# Adafruit_Flora_TCS34725.net
KiCad netlist of a schematic drawn in EAGLE
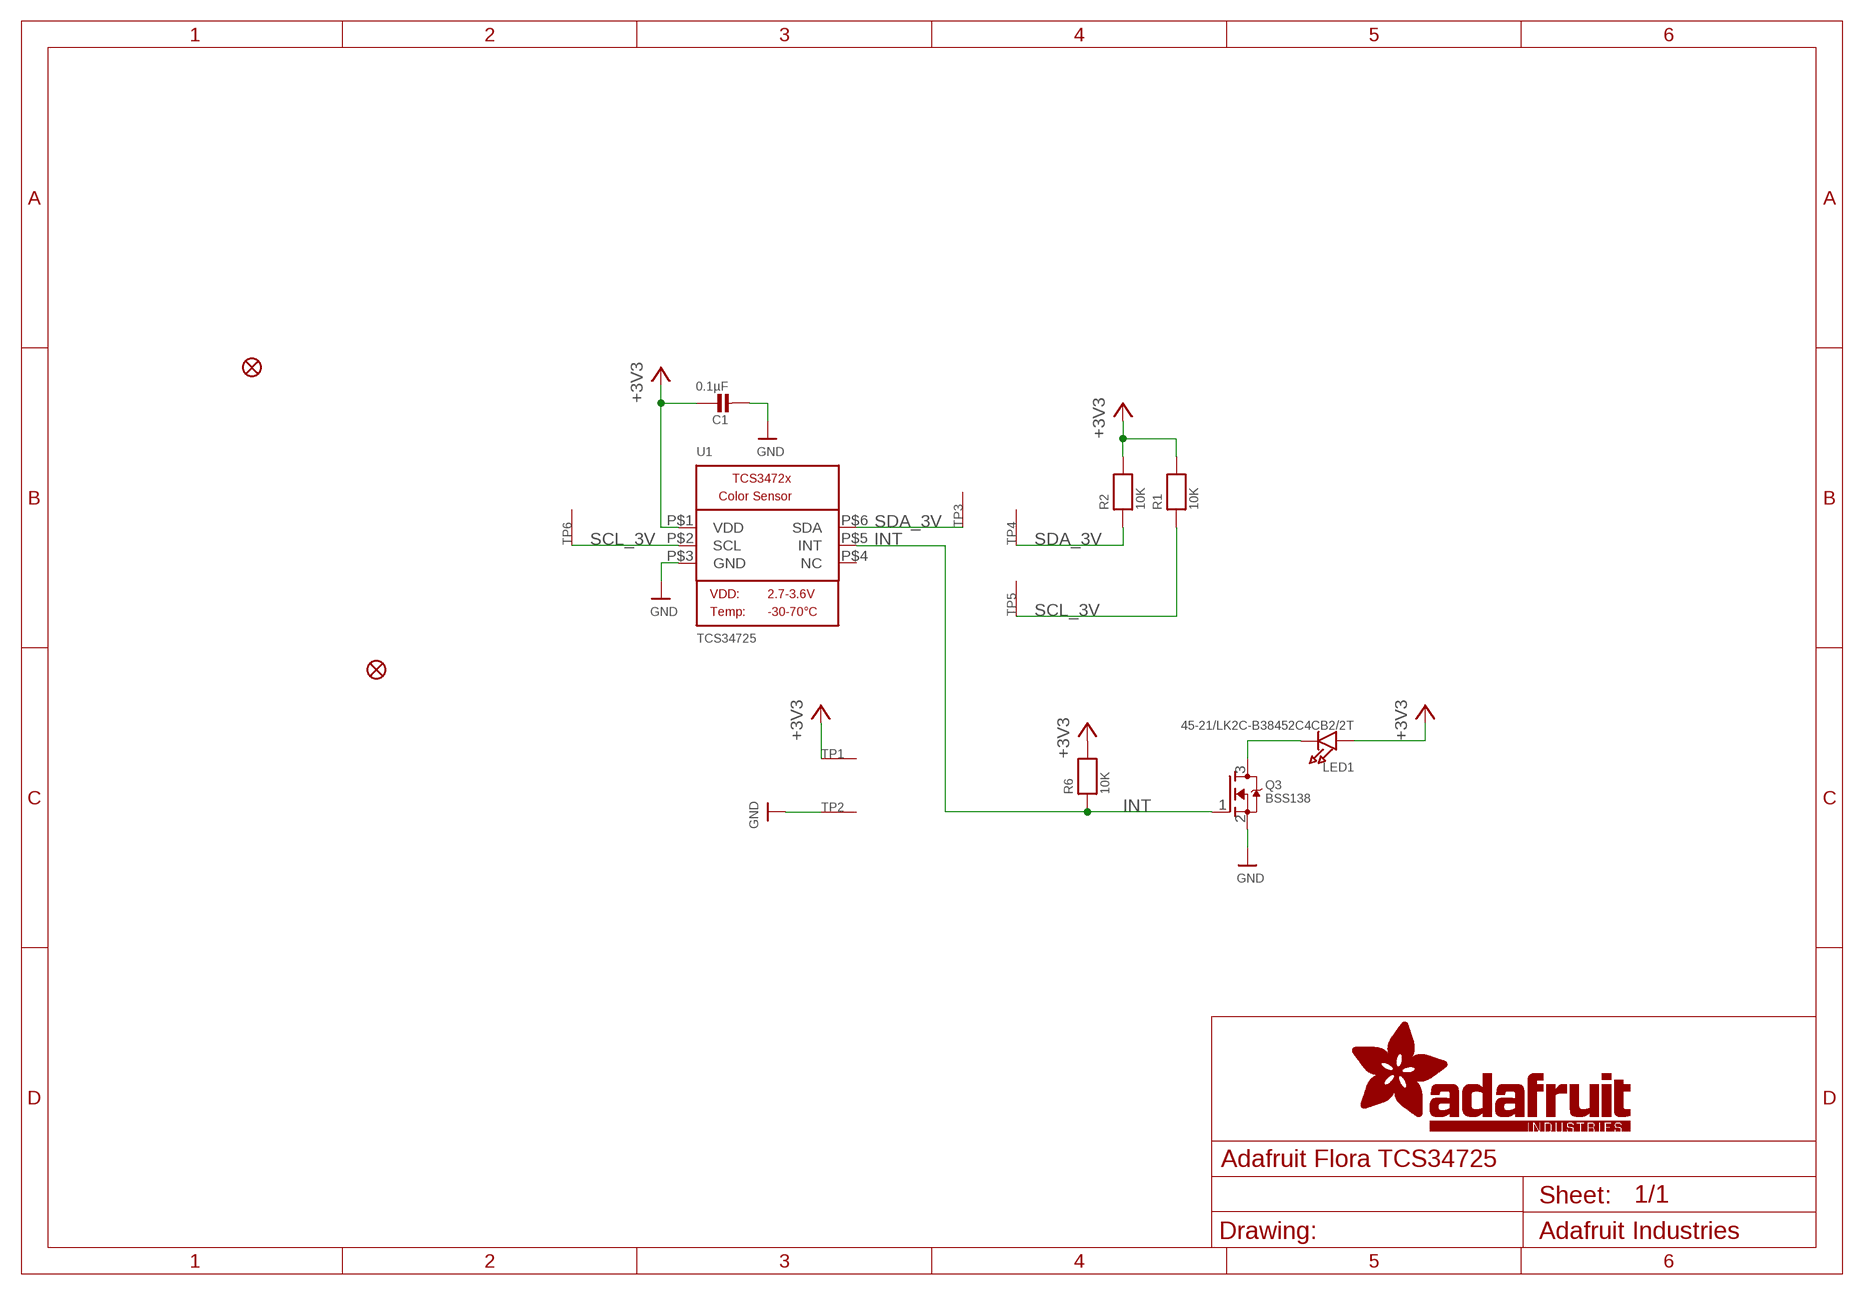
[diagram p0: schematic, sheet 1]

(export (version "E")
  (design (tool "Eeschema 10.0.6"))
  (components
    (comp (ref "C1")
      (value "0.1µF")
      (footprint "eagle-import:_0805")
      (libsource (lib "eagle-import") (part "CAP_CERAMIC_0805"))
    )
    (comp (ref "FID1")
      (value "FIDUCIAL\"\"")
      (footprint "eagle-import:FIDUCIAL_1MM")
      (libsource (lib "eagle-import") (part "FIDUCIAL{dblquote}{dblquote}"))
    )
    (comp (ref "FID2")
      (value "FIDUCIAL\"\"")
      (footprint "eagle-import:FIDUCIAL_1MM")
      (libsource (lib "eagle-import") (part "FIDUCIAL{dblquote}{dblquote}"))
    )
    (comp (ref "LED1")
      (value "45-21/LK2C-B38452C4CB2/2T")
      (footprint "eagle-import:EVERLIGHT_45-21")
      (libsource (lib "eagle-import") (part "LEDEV45-21"))
    )
    (comp (ref "Q3")
      (value "BSS138")
      (footprint "eagle-import:SOT23-WIDE")
      (libsource (lib "eagle-import") (part "MOSFET-NWIDE"))
    )
    (comp (ref "R1")
      (value "10K")
      (footprint "eagle-import:_0805")
      (libsource (lib "eagle-import") (part "RESISTOR_0805"))
    )
    (comp (ref "R2")
      (value "10K")
      (footprint "eagle-import:_0805")
      (libsource (lib "eagle-import") (part "RESISTOR_0805"))
    )
    (comp (ref "R6")
      (value "10K")
      (footprint "eagle-import:_0805")
      (libsource (lib "eagle-import") (part "RESISTOR_0805"))
    )
    (comp (ref "TP1")
      (value "SEWTAP0.5IN")
      (footprint "eagle-import:SEWINGTAP_0.5")
      (libsource (lib "eagle-import") (part "SEWTAP0.5IN"))
    )
    (comp (ref "TP2")
      (value "SEWTAP0.5IN")
      (footprint "eagle-import:SEWINGTAP_0.5")
      (libsource (lib "eagle-import") (part "SEWTAP0.5IN"))
    )
    (comp (ref "TP3")
      (value "SEWTAP0.5IN")
      (footprint "eagle-import:SEWINGTAP_0.5")
      (libsource (lib "eagle-import") (part "SEWTAP0.5IN"))
    )
    (comp (ref "TP4")
      (value "SEWTAP0.5IN")
      (footprint "eagle-import:SEWINGTAP_0.5")
      (libsource (lib "eagle-import") (part "SEWTAP0.5IN"))
    )
    (comp (ref "TP5")
      (value "SEWTAP0.5IN")
      (footprint "eagle-import:SEWINGTAP_0.5")
      (libsource (lib "eagle-import") (part "SEWTAP0.5IN"))
    )
    (comp (ref "TP6")
      (value "SEWTAP0.5IN")
      (footprint "eagle-import:SEWINGTAP_0.5")
      (libsource (lib "eagle-import") (part "SEWTAP0.5IN"))
    )
    (comp (ref "U1")
      (value "TCS34725")
      (footprint "eagle-import:TCS3472_FN6")
      (libsource (lib "eagle-import") (part "LIGHT_TCS3472"))
    )
  )
  (nets
    (net (code "1") (name "+3V3") (class "Default")
      (node (ref "C1") (pin "1") (pinfunction "1_1") (pintype "passive"))
      (node (ref "LED1") (pin "A") (pinfunction "A_A") (pintype "passive"))
      (node (ref "R1") (pin "2") (pinfunction "2_2") (pintype "passive"))
      (node (ref "R2") (pin "2") (pinfunction "2_2") (pintype "passive"))
      (node (ref "R6") (pin "2") (pinfunction "2_2") (pintype "passive"))
      (node (ref "TP1") (pin "TAP") (pinfunction "SEW_TAP") (pintype "bidirectional"))
      (node (ref "U1") (pin "P$1") (pinfunction "VDD_P$1") (pintype "power_in"))
    )
    (net (code "2") (name "/INT") (class "Default")
      (node (ref "Q3") (pin "1") (pinfunction "G_1") (pintype "bidirectional"))
      (node (ref "R6") (pin "1") (pinfunction "1_1") (pintype "passive"))
      (node (ref "U1") (pin "P$5") (pinfunction "INT_P$5") (pintype "output"))
    )
    (net (code "3") (name "/SCL_3V") (class "Default")
      (node (ref "R1") (pin "1") (pinfunction "1_1") (pintype "passive"))
      (node (ref "TP5") (pin "TAP") (pinfunction "SEW_TAP") (pintype "bidirectional"))
      (node (ref "TP6") (pin "TAP") (pinfunction "SEW_TAP") (pintype "bidirectional"))
      (node (ref "U1") (pin "P$2") (pinfunction "SCL_P$2") (pintype "bidirectional"))
    )
    (net (code "4") (name "/SDA_3V") (class "Default")
      (node (ref "R2") (pin "1") (pinfunction "1_1") (pintype "passive"))
      (node (ref "TP3") (pin "TAP") (pinfunction "SEW_TAP") (pintype "bidirectional"))
      (node (ref "TP4") (pin "TAP") (pinfunction "SEW_TAP") (pintype "bidirectional"))
      (node (ref "U1") (pin "P$6") (pinfunction "SDA_P$6") (pintype "bidirectional"))
    )
    (net (code "5") (name "GND") (class "Default")
      (node (ref "C1") (pin "2") (pinfunction "2_2") (pintype "passive"))
      (node (ref "Q3") (pin "2") (pinfunction "S_2") (pintype "bidirectional"))
      (node (ref "TP2") (pin "TAP") (pinfunction "SEW_TAP") (pintype "bidirectional"))
      (node (ref "U1") (pin "P$3") (pinfunction "GND_P$3") (pintype "power_in"))
    )
    (net (code "6") (name "Net-(LED1-C)") (class "Default")
      (node (ref "LED1") (pin "K") (pinfunction "C_K") (pintype "passive"))
      (node (ref "Q3") (pin "3") (pinfunction "D_3") (pintype "bidirectional"))
    )
    (net (code "7") (name "unconnected-(U1-NC-PadP$4)") (class "Default")
      (node (ref "U1") (pin "P$4") (pinfunction "NC_P$4") (pintype "no_connect"))
    )
  )
)
